# Sheet1.net
KiCad netlist of a schematic drawn in Altium Designer
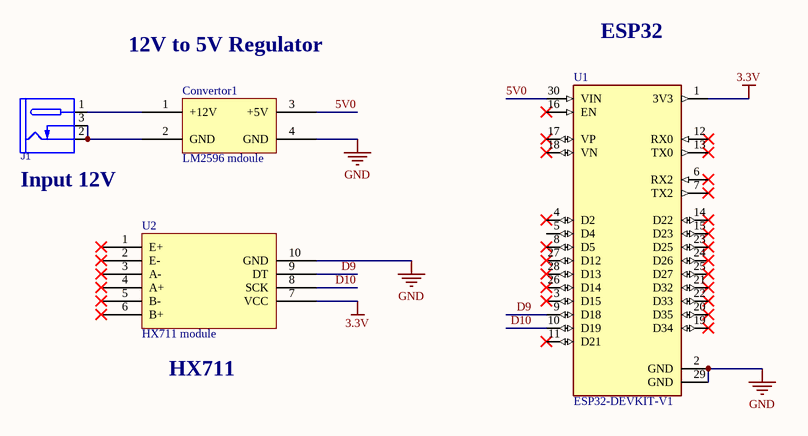
[diagram p0: Sheet1.SchDoc]

(export (version "E")
  (design (tool "Eeschema 10.0.6"))
  (components
    (comp (ref "Convertor1")
      (value "LM2596 mdoule")
      (footprint "DC-DC LM2596")
      (fields (field (name "VOLTAGE") "12V"))
      (libsource (lib "Integrated_Library1") (part "DC-DC LM2596"))
    )
    (comp (ref "J1")
      (value "DC_POWER_JACK")
      (footprint "JAC_PWR2")
      (description "CONN, PWR JACK DC, PLUG DIAM 2.0MM RA THD")
      (fields
        (field (name "MANF") "CUI STACK")
        (field (name "MANF_P#") "PJ-202A, PJ-002AH, PJ-102AH, KLDX-0202")
      )
      (libsource (lib "conn_powerJack") (part "CONN_PWR_JACKR2"))
    )
    (comp (ref "U1")
      (value "ESP32-DEVKIT-V1")
      (footprint "MODULE_ESP32_DEVKIT_V1")
      (fields (field (name "MF") "Do it"))
      (libsource (lib "ESP32-DEVKIT-V1") (part "ESP32-DEVKIT-V1"))
    )
    (comp (ref "U2")
      (value "HX711 module")
      (footprint "HX711")
      (libsource (lib "Integrated_Library1") (part "HX711"))
    )
  )
  (nets
    (net (code "1") (name "/5V0") (class "Default")
      (node (ref "Convertor1") (pin "3") (pinfunction "+5V_3") (pintype "passive"))
      (node (ref "U1") (pin "30") (pinfunction "VIN_30") (pintype "input"))
    )
    (net (code "2") (name "/D9") (class "Default")
      (node (ref "U1") (pin "9") (pinfunction "D18_9") (pintype "bidirectional"))
      (node (ref "U2") (pin "9") (pinfunction "DT_9") (pintype "passive"))
    )
    (net (code "3") (name "/D10") (class "Default")
      (node (ref "U1") (pin "10") (pinfunction "D19_10") (pintype "bidirectional"))
      (node (ref "U2") (pin "8") (pinfunction "SCK_8") (pintype "passive"))
    )
    (net (code "4") (name "3.3V") (class "Default")
      (node (ref "U1") (pin "1") (pinfunction "3V3_1") (pintype "output"))
      (node (ref "U2") (pin "7") (pinfunction "VCC_7") (pintype "passive"))
    )
    (net (code "5") (name "GND") (class "Default")
      (node (ref "Convertor1") (pin "4") (pinfunction "GND_4") (pintype "passive"))
      (node (ref "U1") (pin "2") (pinfunction "GND_2") (pintype "power_in"))
      (node (ref "U1") (pin "29") (pinfunction "GND_29") (pintype "power_in"))
      (node (ref "U2") (pin "10") (pinfunction "GND_10") (pintype "passive"))
    )
    (net (code "6") (name "Net-(Convertor1-+12V)") (class "Default")
      (node (ref "Convertor1") (pin "1") (pinfunction "+12V_1") (pintype "passive"))
      (node (ref "J1") (pin "1") (pinfunction "TIP_1") (pintype "power_in"))
    )
    (net (code "7") (name "Net-(J1-INSERTION_DET)") (class "Default")
      (node (ref "Convertor1") (pin "2") (pinfunction "GND_2") (pintype "passive"))
      (node (ref "J1") (pin "2") (pinfunction "SLEEVE_2") (pintype "power_in"))
      (node (ref "J1") (pin "3") (pinfunction "INSERTION_DET_3") (pintype "power_in"))
    )
    (net (code "8") (name "unconnected-(U1-D2-Pad4)") (class "Default")
      (node (ref "U1") (pin "4") (pinfunction "D2_4") (pintype "bidirectional+no_connect"))
    )
    (net (code "9") (name "unconnected-(U1-D4-Pad5)") (class "Default")
      (node (ref "U1") (pin "5") (pinfunction "D4_5") (pintype "bidirectional"))
    )
    (net (code "10") (name "unconnected-(U1-D5-Pad8)") (class "Default")
      (node (ref "U1") (pin "8") (pinfunction "D5_8") (pintype "bidirectional+no_connect"))
    )
    (net (code "11") (name "unconnected-(U1-D12-Pad27)") (class "Default")
      (node (ref "U1") (pin "27") (pinfunction "D12_27") (pintype "bidirectional+no_connect"))
    )
    (net (code "12") (name "unconnected-(U1-D13-Pad28)") (class "Default")
      (node (ref "U1") (pin "28") (pinfunction "D13_28") (pintype "bidirectional+no_connect"))
    )
    (net (code "13") (name "unconnected-(U1-D14-Pad26)") (class "Default")
      (node (ref "U1") (pin "26") (pinfunction "D14_26") (pintype "bidirectional+no_connect"))
    )
    (net (code "14") (name "unconnected-(U1-D15-Pad3)") (class "Default")
      (node (ref "U1") (pin "3") (pinfunction "D15_3") (pintype "bidirectional+no_connect"))
    )
    (net (code "15") (name "unconnected-(U1-D21-Pad11)") (class "Default")
      (node (ref "U1") (pin "11") (pinfunction "D21_11") (pintype "bidirectional+no_connect"))
    )
    (net (code "16") (name "unconnected-(U1-D22-Pad14)") (class "Default")
      (node (ref "U1") (pin "14") (pinfunction "D22_14") (pintype "bidirectional+no_connect"))
    )
    (net (code "17") (name "unconnected-(U1-D23-Pad15)") (class "Default")
      (node (ref "U1") (pin "15") (pinfunction "D23_15") (pintype "bidirectional+no_connect"))
    )
    (net (code "18") (name "unconnected-(U1-D25-Pad23)") (class "Default")
      (node (ref "U1") (pin "23") (pinfunction "D25_23") (pintype "bidirectional+no_connect"))
    )
    (net (code "19") (name "unconnected-(U1-D26-Pad24)") (class "Default")
      (node (ref "U1") (pin "24") (pinfunction "D26_24") (pintype "bidirectional+no_connect"))
    )
    (net (code "20") (name "unconnected-(U1-D27-Pad25)") (class "Default")
      (node (ref "U1") (pin "25") (pinfunction "D27_25") (pintype "bidirectional+no_connect"))
    )
    (net (code "21") (name "unconnected-(U1-D32-Pad21)") (class "Default")
      (node (ref "U1") (pin "21") (pinfunction "D32_21") (pintype "bidirectional+no_connect"))
    )
    (net (code "22") (name "unconnected-(U1-D33-Pad22)") (class "Default")
      (node (ref "U1") (pin "22") (pinfunction "D33_22") (pintype "bidirectional+no_connect"))
    )
    (net (code "23") (name "unconnected-(U1-D34-Pad19)") (class "Default")
      (node (ref "U1") (pin "19") (pinfunction "D34_19") (pintype "bidirectional+no_connect"))
    )
    (net (code "24") (name "unconnected-(U1-D35-Pad20)") (class "Default")
      (node (ref "U1") (pin "20") (pinfunction "D35_20") (pintype "bidirectional+no_connect"))
    )
    (net (code "25") (name "unconnected-(U1-EN-Pad16)") (class "Default")
      (node (ref "U1") (pin "16") (pinfunction "EN_16") (pintype "input+no_connect"))
    )
    (net (code "26") (name "unconnected-(U1-RX0-Pad12)") (class "Default")
      (node (ref "U1") (pin "12") (pinfunction "RX0_12") (pintype "input+no_connect"))
    )
    (net (code "27") (name "unconnected-(U1-RX2-Pad6)") (class "Default")
      (node (ref "U1") (pin "6") (pinfunction "RX2_6") (pintype "input+no_connect"))
    )
    (net (code "28") (name "unconnected-(U1-TX0-Pad13)") (class "Default")
      (node (ref "U1") (pin "13") (pinfunction "TX0_13") (pintype "output+no_connect"))
    )
    (net (code "29") (name "unconnected-(U1-TX2-Pad7)") (class "Default")
      (node (ref "U1") (pin "7") (pinfunction "TX2_7") (pintype "output+no_connect"))
    )
    (net (code "30") (name "unconnected-(U1-VN-Pad18)") (class "Default")
      (node (ref "U1") (pin "18") (pinfunction "VN_18") (pintype "bidirectional+no_connect"))
    )
    (net (code "31") (name "unconnected-(U1-VP-Pad17)") (class "Default")
      (node (ref "U1") (pin "17") (pinfunction "VP_17") (pintype "bidirectional+no_connect"))
    )
    (net (code "32") (name "unconnected-(U2-A+-Pad4)") (class "Default")
      (node (ref "U2") (pin "4") (pinfunction "A+_4") (pintype "passive+no_connect"))
    )
    (net (code "33") (name "unconnected-(U2-A--Pad3)") (class "Default")
      (node (ref "U2") (pin "3") (pinfunction "A-_3") (pintype "passive+no_connect"))
    )
    (net (code "34") (name "unconnected-(U2-B+-Pad6)") (class "Default")
      (node (ref "U2") (pin "6") (pinfunction "B+_6") (pintype "passive+no_connect"))
    )
    (net (code "35") (name "unconnected-(U2-B--Pad5)") (class "Default")
      (node (ref "U2") (pin "5") (pinfunction "B-_5") (pintype "passive+no_connect"))
    )
    (net (code "36") (name "unconnected-(U2-E+-Pad1)") (class "Default")
      (node (ref "U2") (pin "1") (pinfunction "E+_1") (pintype "passive+no_connect"))
    )
    (net (code "37") (name "unconnected-(U2-E--Pad2)") (class "Default")
      (node (ref "U2") (pin "2") (pinfunction "E-_2") (pintype "passive+no_connect"))
    )
  )
)
